# JACK_DUAL_M1_V6.net
KiCad netlist of a schematic drawn in EAGLE
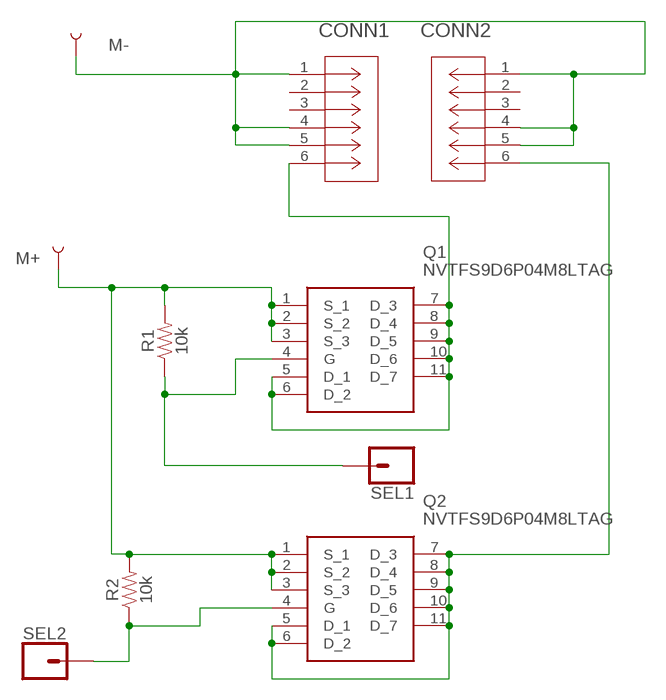
[diagram p0: schematic, sheet 1]

(export (version "E")
  (design (tool "Eeschema 10.0.6"))
  (components
    (comp (ref "CONN1")
      (value "ACJS-MHDR")
      (footprint "eagle-import:CONN_MHDR_AMP")
      (fields (field (name "COPYRIGHT") "Copyright (C) 2018 Accelerated Designs. All rights reserved"))
      (libsource (lib "eagle-import") (part "ACJS-MHDR"))
    )
    (comp (ref "CONN2")
      (value "ACJS-MHDR")
      (footprint "eagle-import:CONN_MHDR_AMP")
      (fields (field (name "COPYRIGHT") "Copyright (C) 2018 Accelerated Designs. All rights reserved"))
      (libsource (lib "eagle-import") (part "ACJS-MHDR"))
    )
    (comp (ref "M+")
      (value "TEST-POINT3")
      (footprint "eagle-import:PAD.03X.03")
      (libsource (lib "eagle-import") (part "TEST-POINT3"))
    )
    (comp (ref "M-")
      (value "TEST-POINT3")
      (footprint "eagle-import:PAD.03X.03")
      (libsource (lib "eagle-import") (part "TEST-POINT3"))
    )
    (comp (ref "Q1")
      (value "NVTFS9D6P04M8LTAG")
      (footprint "eagle-import:NVTFS5124PLTWG")
      (fields (field (name "MOUSER_PART_NUMBER") "863-NVTFS9D6P04M8LTG"))
      (libsource (lib "eagle-import") (part "NVTFS9D6P04M8LTAG"))
    )
    (comp (ref "Q2")
      (value "NVTFS9D6P04M8LTAG")
      (footprint "eagle-import:NVTFS5124PLTWG")
      (fields (field (name "MOUSER_PART_NUMBER") "863-NVTFS9D6P04M8LTG"))
      (libsource (lib "eagle-import") (part "NVTFS9D6P04M8LTAG"))
    )
    (comp (ref "R1")
      (value "10k")
      (footprint "eagle-import:0805")
      (libsource (lib "eagle-import") (part "RESISTOR0805"))
    )
    (comp (ref "R2")
      (value "10k")
      (footprint "eagle-import:0805")
      (libsource (lib "eagle-import") (part "RESISTOR0805"))
    )
    (comp (ref "SEL1")
      (value "CONN_01")
      (footprint "eagle-import:1X01")
      (libsource (lib "eagle-import") (part "CONN_01"))
    )
    (comp (ref "SEL2")
      (value "CONN_01")
      (footprint "eagle-import:1X01")
      (libsource (lib "eagle-import") (part "CONN_01"))
    )
  )
  (nets
    (net (code "1") (name "Net-(M+-1)") (class "Default")
      (node (ref "M+") (pin "P$1") (pinfunction "1_P$1") (pintype "bidirectional"))
      (node (ref "Q1") (pin "1") (pinfunction "S_1_1") (pintype "bidirectional"))
      (node (ref "Q1") (pin "2") (pinfunction "S_2_2") (pintype "bidirectional"))
      (node (ref "Q1") (pin "3") (pinfunction "S_3_3") (pintype "bidirectional"))
      (node (ref "Q2") (pin "1") (pinfunction "S_1_1") (pintype "bidirectional"))
      (node (ref "Q2") (pin "2") (pinfunction "S_2_2") (pintype "bidirectional"))
      (node (ref "Q2") (pin "3") (pinfunction "S_3_3") (pintype "bidirectional"))
      (node (ref "R1") (pin "2") (pinfunction "2_2") (pintype "passive"))
      (node (ref "R2") (pin "2") (pinfunction "2_2") (pintype "passive"))
    )
    (net (code "2") (name "Net-(M--1)") (class "Default")
      (node (ref "CONN1") (pin "1") (pinfunction "1_1") (pintype "passive"))
      (node (ref "CONN1") (pin "4") (pinfunction "4_4") (pintype "passive"))
      (node (ref "CONN1") (pin "5") (pinfunction "5_5") (pintype "passive"))
      (node (ref "CONN2") (pin "1") (pinfunction "1_1") (pintype "passive"))
      (node (ref "CONN2") (pin "4") (pinfunction "4_4") (pintype "passive"))
      (node (ref "CONN2") (pin "5") (pinfunction "5_5") (pintype "passive"))
      (node (ref "M-") (pin "P$1") (pinfunction "1_P$1") (pintype "bidirectional"))
    )
    (net (code "3") (name "Net-(Q1-D_1)") (class "Default")
      (node (ref "CONN1") (pin "6") (pinfunction "6_6") (pintype "passive"))
      (node (ref "Q1") (pin "10") (pinfunction "D_6_10") (pintype "bidirectional"))
      (node (ref "Q1") (pin "11") (pinfunction "D_7_11") (pintype "bidirectional"))
      (node (ref "Q1") (pin "5") (pinfunction "D_1_5") (pintype "bidirectional"))
      (node (ref "Q1") (pin "6") (pinfunction "D_2_6") (pintype "bidirectional"))
      (node (ref "Q1") (pin "7") (pinfunction "D_3_7") (pintype "bidirectional"))
      (node (ref "Q1") (pin "8") (pinfunction "D_4_8") (pintype "bidirectional"))
      (node (ref "Q1") (pin "9") (pinfunction "D_5_9") (pintype "bidirectional"))
    )
    (net (code "4") (name "Net-(Q1-G)") (class "Default")
      (node (ref "Q1") (pin "4") (pinfunction "G_4") (pintype "bidirectional"))
      (node (ref "R1") (pin "1") (pinfunction "1_1") (pintype "passive"))
      (node (ref "SEL1") (pin "1") (pinfunction "1_1") (pintype "passive"))
    )
    (net (code "5") (name "Net-(Q2-D_1)") (class "Default")
      (node (ref "CONN2") (pin "6") (pinfunction "6_6") (pintype "passive"))
      (node (ref "Q2") (pin "10") (pinfunction "D_6_10") (pintype "bidirectional"))
      (node (ref "Q2") (pin "11") (pinfunction "D_7_11") (pintype "bidirectional"))
      (node (ref "Q2") (pin "5") (pinfunction "D_1_5") (pintype "bidirectional"))
      (node (ref "Q2") (pin "6") (pinfunction "D_2_6") (pintype "bidirectional"))
      (node (ref "Q2") (pin "7") (pinfunction "D_3_7") (pintype "bidirectional"))
      (node (ref "Q2") (pin "8") (pinfunction "D_4_8") (pintype "bidirectional"))
      (node (ref "Q2") (pin "9") (pinfunction "D_5_9") (pintype "bidirectional"))
    )
    (net (code "6") (name "Net-(Q2-G)") (class "Default")
      (node (ref "Q2") (pin "4") (pinfunction "G_4") (pintype "bidirectional"))
      (node (ref "R2") (pin "1") (pinfunction "1_1") (pintype "passive"))
      (node (ref "SEL2") (pin "1") (pinfunction "1_1") (pintype "passive"))
    )
    (net (code "7") (name "unconnected-(CONN1-Pad2)") (class "Default")
      (node (ref "CONN1") (pin "2") (pinfunction "2_2") (pintype "passive"))
    )
    (net (code "8") (name "unconnected-(CONN1-Pad3)") (class "Default")
      (node (ref "CONN1") (pin "3") (pinfunction "3_3") (pintype "passive"))
    )
    (net (code "9") (name "unconnected-(CONN2-Pad2)") (class "Default")
      (node (ref "CONN2") (pin "2") (pinfunction "2_2") (pintype "passive"))
    )
    (net (code "10") (name "unconnected-(CONN2-Pad3)") (class "Default")
      (node (ref "CONN2") (pin "3") (pinfunction "3_3") (pintype "passive"))
    )
  )
)
